# Auxiliary_Horn.net
KiCad netlist of a schematic drawn in Altium Designer
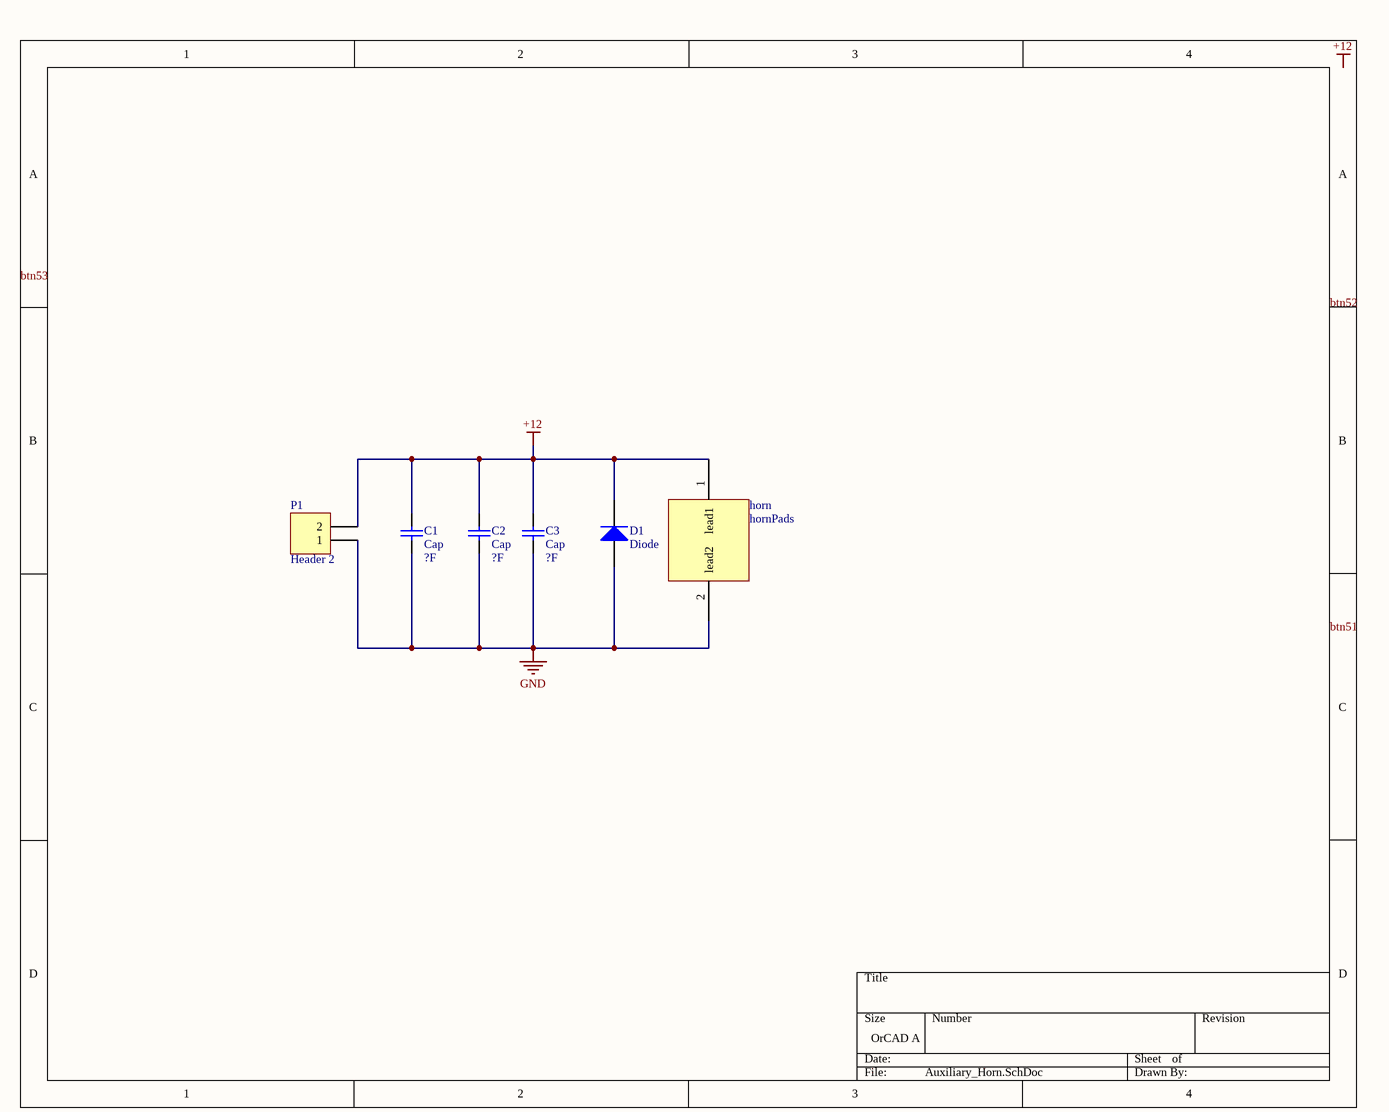
[diagram p0: Auxiliary_Horn.SchDoc]

(export (version "E")
  (design (tool "Eeschema 10.0.6"))
  (components
    (comp (ref "C1")
      (value "Cap")
      (footprint "RAD-0.3")
      (description "Capacitor")
      (fields (field (name "ALTIUM_VALUE") "?F") (field (name "PUBLISHER") "Altium Limited"))
      (libsource (lib "Miscellaneous Devices") (part "Cap"))
    )
    (comp (ref "C2")
      (value "Cap")
      (footprint "RAD-0.3")
      (description "Capacitor")
      (fields (field (name "ALTIUM_VALUE") "?F") (field (name "PUBLISHER") "Altium Limited"))
      (libsource (lib "Miscellaneous Devices") (part "Cap"))
    )
    (comp (ref "C3")
      (value "Cap")
      (footprint "RAD-0.3")
      (description "Capacitor")
      (fields (field (name "ALTIUM_VALUE") "?F") (field (name "PUBLISHER") "Altium Limited"))
      (libsource (lib "Miscellaneous Devices") (part "Cap"))
    )
    (comp (ref "D1")
      (value "Diode")
      (footprint "SMC")
      (description "Default Diode")
      (fields (field (name "PUBLISHER") "Altium Limited"))
      (libsource (lib "Miscellaneous Devices") (part "Diode"))
    )
    (comp (ref "horn") (value "hornPads") (footprint "Horn_Pads") (libsource (lib "Horn") (part "hornPads")))
    (comp (ref "P1")
      (value "Header 2")
      (footprint "HDR1X2")
      (description "Header, 2-Pin")
      (fields (field (name "PUBLISHER") "Altium Limited"))
      (libsource (lib "Miscellaneous Connectors") (part "Header 2"))
    )
  )
  (nets
    (net (code "1") (name "+12") (class "Default")
      (node (ref "C1") (pin "2") (pinfunction "2_2") (pintype "passive"))
      (node (ref "C2") (pin "2") (pinfunction "2_2") (pintype "passive"))
      (node (ref "C3") (pin "2") (pinfunction "2_2") (pintype "passive"))
      (node (ref "D1") (pin "2") (pinfunction "K_2") (pintype "passive"))
      (node (ref "P1") (pin "2") (pinfunction "2_2") (pintype "passive"))
      (node (ref "horn") (pin "1") (pinfunction "lead1_1") (pintype "passive"))
    )
    (net (code "5") (name "GND") (class "Default")
      (node (ref "C1") (pin "1") (pinfunction "1_1") (pintype "passive"))
      (node (ref "C2") (pin "1") (pinfunction "1_1") (pintype "passive"))
      (node (ref "C3") (pin "1") (pinfunction "1_1") (pintype "passive"))
      (node (ref "D1") (pin "1") (pinfunction "A_1") (pintype "passive"))
      (node (ref "P1") (pin "1") (pinfunction "1_1") (pintype "passive"))
      (node (ref "horn") (pin "2") (pinfunction "lead2_2") (pintype "passive"))
    )
  )
)
